# Sheet2.net
KiCad netlist of a schematic drawn in Altium Designer
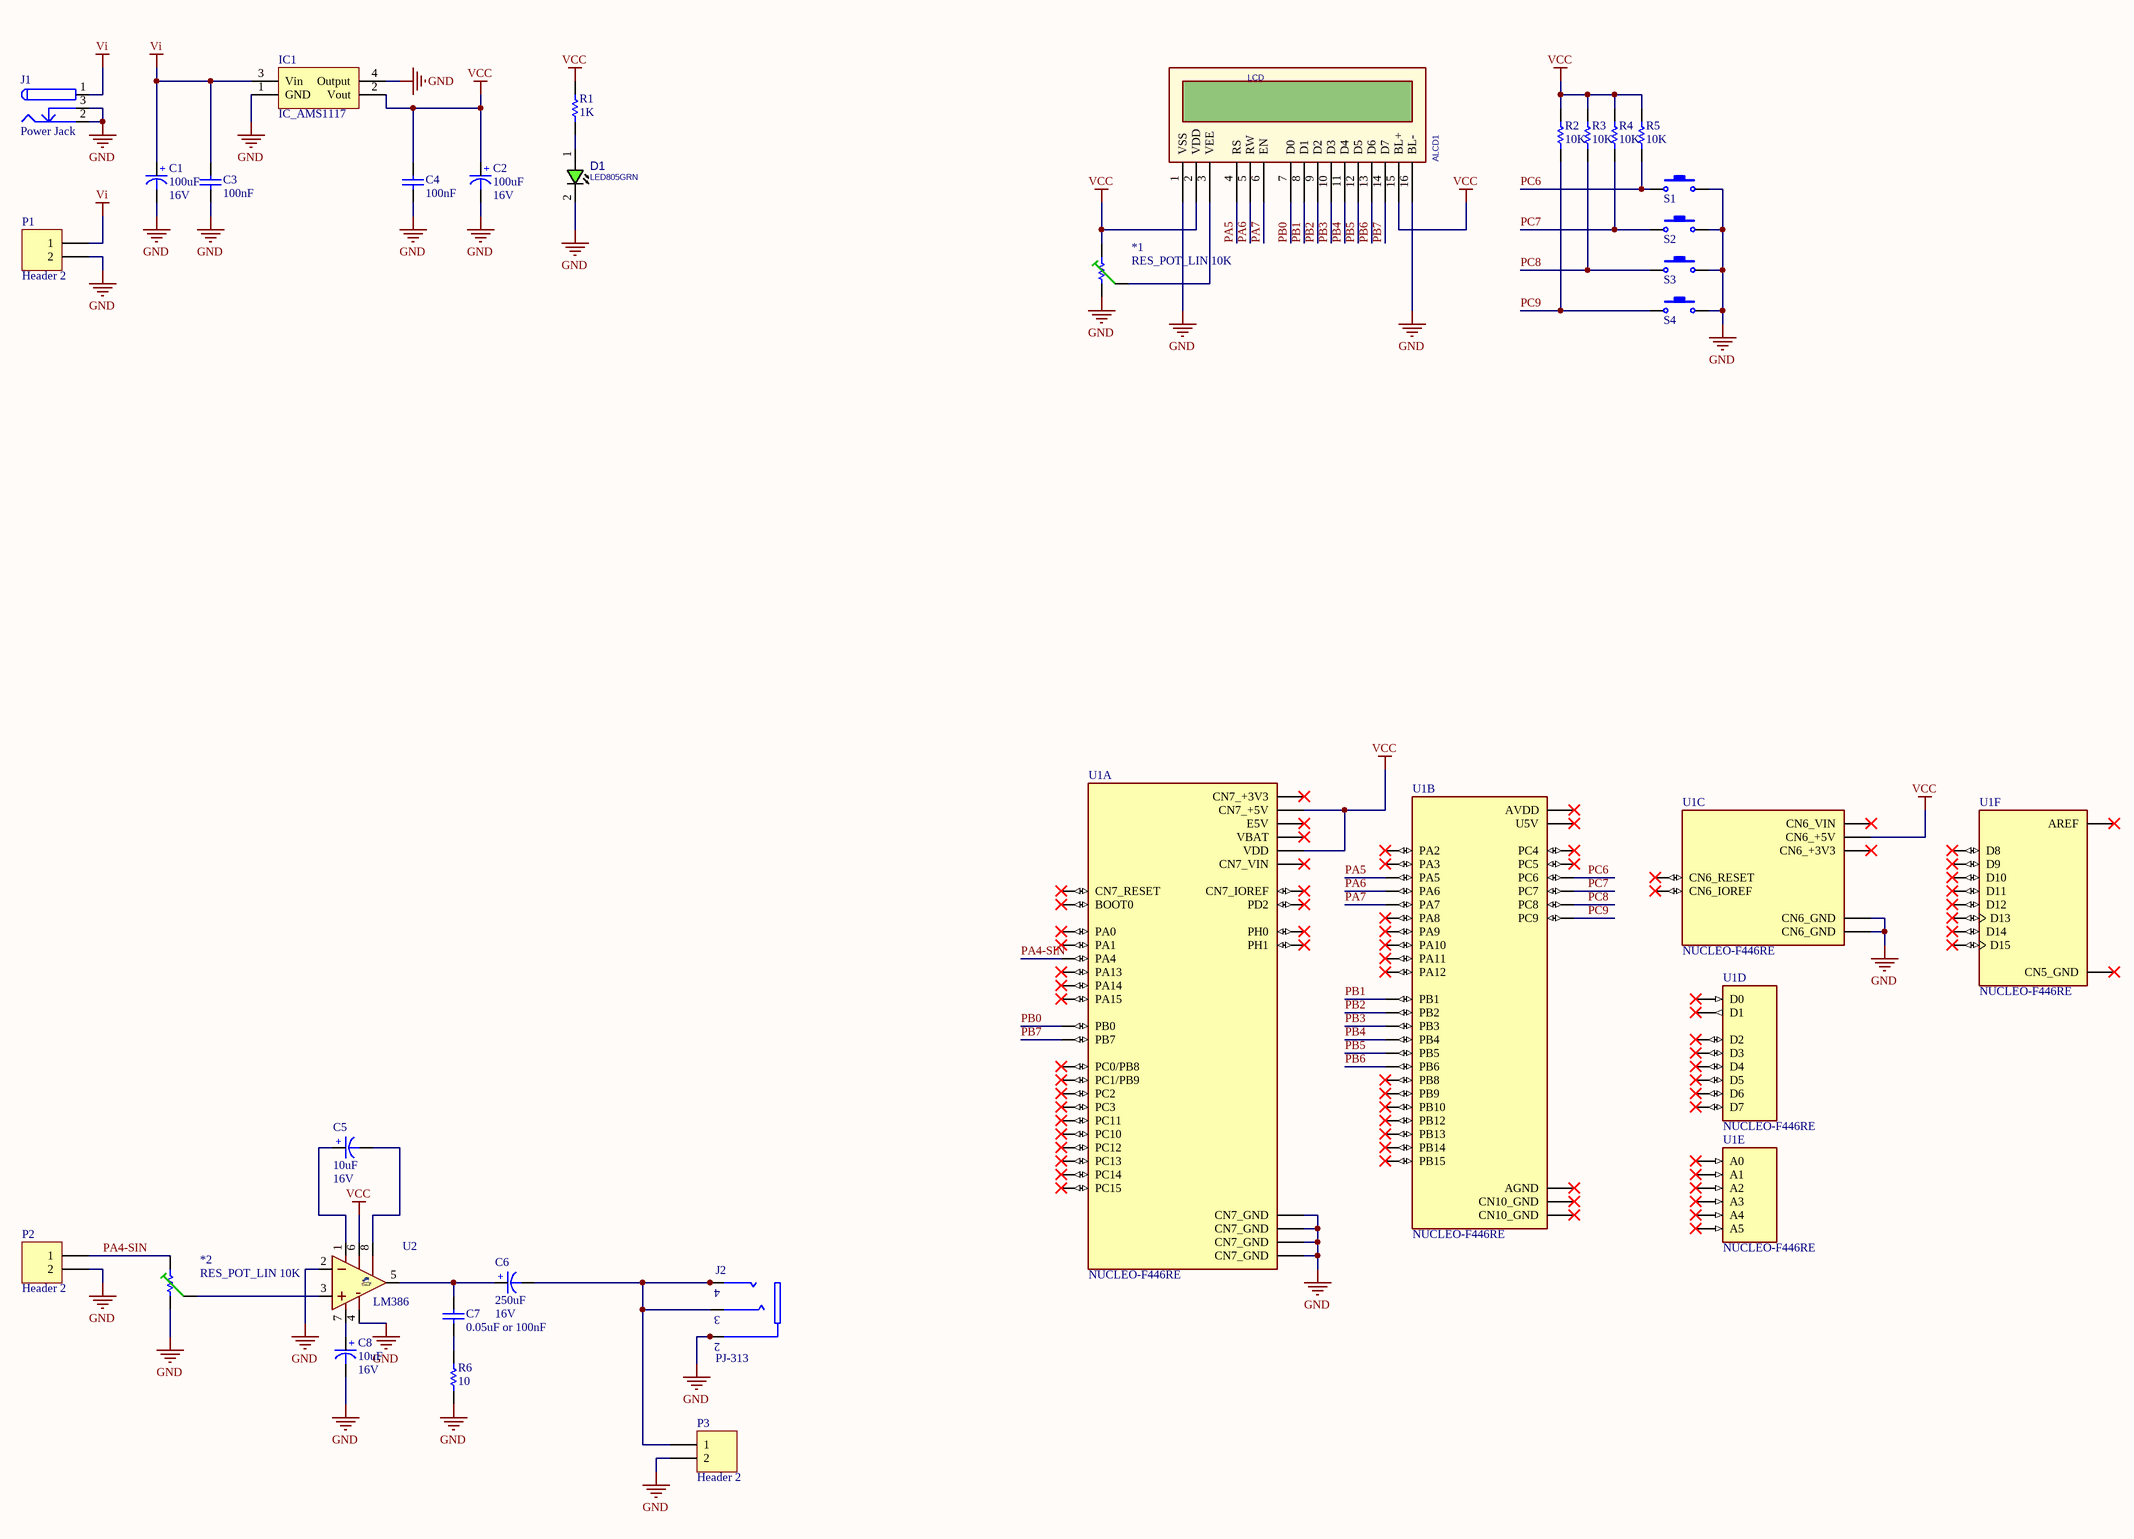
[diagram p0: Sheet2.SchDoc]

(export (version "E")
  (design (tool "Eeschema 10.0.6"))
  (components
    (comp (ref "*1")
      (value "RES_POT_LIN 10K")
      (footprint "3296W")
      (libsource (lib "Passive Components") (part "RES_POT_LIN"))
    )
    (comp (ref "*2")
      (value "RES_POT_LIN 10K")
      (footprint "3296W")
      (libsource (lib "Passive Components") (part "RES_POT_LIN"))
    )
    (comp (ref "ALCD1")
      (value "LCD")
      (footprint "LCD_2X16 GREEN10mm")
      (description "Alphanumic LCD")
      (fields (field (name "DESIGNER") "Abbas Basereh"))
      (libsource (lib "Altium") (part "LCD"))
    )
    (comp (ref "C1")
      (value "100uF")
      (footprint "cap 01")
      (description "Polar Capacitor")
      (fields (field (name "VOLTAGE") "16V") (field (name "DESIGNER") "Saeid Jorablo"))
      (libsource (lib "My_Library") (part "Cap-Polar"))
    )
    (comp (ref "C2")
      (value "100uF")
      (footprint "cap 01")
      (description "Polar Capacitor")
      (fields (field (name "VOLTAGE") "16V") (field (name "DESIGNER") "Saeid Jorablo"))
      (libsource (lib "My_Library") (part "Cap-Polar"))
    )
    (comp (ref "C3")
      (value "100nF")
      (footprint "CAPC3413X12N")
      (description "CAP 0805")
      (fields (field (name "DESIGNER") "Abbas Basereh"))
      (libsource (lib "Altium") (part "CAP SMD 0805"))
    )
    (comp (ref "C4")
      (value "100nF")
      (footprint "CAPC3413X12N")
      (description "CAP 0805")
      (fields (field (name "DESIGNER") "Abbas Basereh"))
      (libsource (lib "Altium") (part "CAP SMD 0805"))
    )
    (comp (ref "C5")
      (value "10uF")
      (footprint "cap 01")
      (description "Polar Capacitor")
      (fields (field (name "VOLTAGE") "16V") (field (name "DESIGNER") "Saeid Jorablo"))
      (libsource (lib "My_Library") (part "Cap-Polar"))
    )
    (comp (ref "C6")
      (value "250uF")
      (footprint "cap 01")
      (description "Polar Capacitor")
      (fields (field (name "VOLTAGE") "16V") (field (name "DESIGNER") "Saeid Jorablo"))
      (libsource (lib "My_Library") (part "Cap-Polar"))
    )
    (comp (ref "C7")
      (value "0.05uF or 100nF")
      (footprint "CAPC3413X12N")
      (description "CAP 0805")
      (fields (field (name "DESIGNER") "Abbas Basereh"))
      (libsource (lib "Altium") (part "CAP SMD 0805"))
    )
    (comp (ref "C8")
      (value "10uF")
      (footprint "cap 01")
      (description "Polar Capacitor")
      (fields (field (name "VOLTAGE") "16V") (field (name "DESIGNER") "Saeid Jorablo"))
      (libsource (lib "My_Library") (part "Cap-Polar"))
    )
    (comp (ref "D1")
      (value "LED805GRN")
      (footprint "LED0805GRN")
      (description "LED, SMD, 0805, GREEN")
      (libsource (lib "led(diode)") (part "LED_SMD_0805_GRN"))
    )
    (comp (ref "IC1")
      (value "IC_AMS1117")
      (footprint "SOT223-4N")
      (description "800mA LOW DROPOUT VOLTAGE REGULATOR")
      (fields
        (field (name "MANUFACTURER") "Advanced Monolithic Systems, Inc.")
        (field (name "DESIGNER") "Eng. Saeid Jorablo")
      )
      (libsource (lib "General 3") (part "IC_AMS1117"))
    )
    (comp (ref "J1")
      (value "Power Jack")
      (footprint "Power Jack")
      (fields (field (name "DESIGNER") "Saeid Jorablo"))
      (libsource (lib "General 2") (part "Power Jack"))
    )
    (comp (ref "J2")
      (value "PJ-313")
      (footprint "PJ-313")
      (description "DC DC Converter Output Input")
      (fields (field (name "MF") "ADC Telecommunications") (field (name "MP") "PJ313"))
      (libsource (lib "PJ-313") (part "PJ-313"))
    )
    (comp (ref "P1")
      (value "Header 2")
      (footprint "HDR1X2")
      (description "Header, 2-Pin")
      (fields (field (name "PUBLISHER") "Altium Limited"))
      (libsource (lib "Altium") (part "Header 2"))
    )
    (comp (ref "P2")
      (value "Header 2")
      (footprint "HDR1X2")
      (description "Header, 2-Pin")
      (fields (field (name "PUBLISHER") "Altium Limited"))
      (libsource (lib "Altium") (part "Header 2"))
    )
    (comp (ref "P3")
      (value "Header 2")
      (footprint "CON_MKDSN1,5/2-5,08")
      (description "Header, 2-Pin")
      (fields (field (name "PUBLISHER") "Altium Limited"))
      (libsource (lib "") (part "Header 2_1"))
    )
    (comp (ref "R1")
      (value "1K")
      (footprint "RESC3413X04N")
      (description "RES 0805")
      (fields (field (name "DESIGNER") "Abbas Basereh"))
      (libsource (lib "General 1") (part "RES 0805 0.125W"))
    )
    (comp (ref "R2")
      (value "10K")
      (footprint "RESC3413X04N")
      (description "RES 0805")
      (fields (field (name "DESIGNER") "Abbas Basereh"))
      (libsource (lib "General 1") (part "RES 0805 0.125W"))
    )
    (comp (ref "R3")
      (value "10K")
      (footprint "RESC3413X04N")
      (description "RES 0805")
      (fields (field (name "DESIGNER") "Abbas Basereh"))
      (libsource (lib "General 1") (part "RES 0805 0.125W"))
    )
    (comp (ref "R4")
      (value "10K")
      (footprint "RESC3413X04N")
      (description "RES 0805")
      (fields (field (name "DESIGNER") "Abbas Basereh"))
      (libsource (lib "General 1") (part "RES 0805 0.125W"))
    )
    (comp (ref "R5")
      (value "10K")
      (footprint "RESC3413X04N")
      (description "RES 0805")
      (fields (field (name "DESIGNER") "Abbas Basereh"))
      (libsource (lib "General 1") (part "RES 0805 0.125W"))
    )
    (comp (ref "R6")
      (value "10")
      (footprint "RESC3413X04N")
      (description "RES 0805")
      (fields (field (name "DESIGNER") "Abbas Basereh"))
      (libsource (lib "General 1") (part "RES 0805 0.125W"))
    )
    (comp (ref "S1")
      (value "Switch PB")
      (footprint "SWPBT_SPST_6X6X10")
      (description "Push Button Switch")
      (libsource (lib "Altium") (part "Switch PB"))
    )
    (comp (ref "S2")
      (value "Switch PB")
      (footprint "SWPBT_SPST_6X6X10")
      (description "Push Button Switch")
      (libsource (lib "Altium") (part "Switch PB"))
    )
    (comp (ref "S3")
      (value "Switch PB")
      (footprint "SWPBT_SPST_6X6X10")
      (description "Push Button Switch")
      (libsource (lib "Altium") (part "Switch PB"))
    )
    (comp (ref "S4")
      (value "Switch PB")
      (footprint "SWPBT_SPST_6X6X10")
      (description "Push Button Switch")
      (libsource (lib "Altium") (part "Switch PB"))
    )
    (comp (ref "U1")
      (value "NUCLEO-F446RE")
      (footprint "MODULE_NUCLEO-F446RE")
      (libsource (lib "NUCLEO-F446RE") (part "NUCLEO-F446RE"))
    )
    (comp (ref "U2")
      (value "LM386")
      (footprint "DIP8")
      (description "AMP, Audio, Low Voltage, Power Amp")
      (fields (field (name "MANF") "Texas Instruments") (field (name "MANF_P#") "LM386N-1"))
      (libsource (lib "amp_audio") (part "LM386_DIP8"))
    )
  )
  (nets
    (net (code "1") (name "/PA4-SIN") (class "Default")
      (node (ref "*2") (pin "1") (pinfunction "CCW_1") (pintype "passive"))
      (node (ref "P2") (pin "1") (pinfunction "1_1") (pintype "passive"))
      (node (ref "U1") (pin "CN7_32") (pinfunction "PA4_CN7_32") (pintype "bidirectional"))
    )
    (net (code "2") (name "/PA5") (class "Default")
      (node (ref "ALCD1") (pin "4") (pinfunction "RS_4") (pintype "passive"))
      (node (ref "U1") (pin "CN10_11") (pinfunction "PA5_CN10_11") (pintype "bidirectional"))
    )
    (net (code "3") (name "/PA6") (class "Default")
      (node (ref "ALCD1") (pin "5") (pinfunction "RW_5") (pintype "passive"))
      (node (ref "U1") (pin "CN10_13") (pinfunction "PA6_CN10_13") (pintype "bidirectional"))
    )
    (net (code "4") (name "/PA7") (class "Default")
      (node (ref "ALCD1") (pin "6") (pinfunction "EN_6") (pintype "passive"))
      (node (ref "U1") (pin "CN10_15") (pinfunction "PA7_CN10_15") (pintype "bidirectional"))
    )
    (net (code "5") (name "/PB0") (class "Default")
      (node (ref "ALCD1") (pin "7") (pinfunction "D0_7") (pintype "passive"))
      (node (ref "U1") (pin "CN7_34") (pinfunction "PB0_CN7_34") (pintype "bidirectional"))
    )
    (net (code "6") (name "/PB1") (class "Default")
      (node (ref "ALCD1") (pin "8") (pinfunction "D1_8") (pintype "passive"))
      (node (ref "U1") (pin "CN10_24") (pinfunction "PB1_CN10_24") (pintype "bidirectional"))
    )
    (net (code "7") (name "/PB2") (class "Default")
      (node (ref "ALCD1") (pin "9") (pinfunction "D2_9") (pintype "passive"))
      (node (ref "U1") (pin "CN10_22") (pinfunction "PB2_CN10_22") (pintype "bidirectional"))
    )
    (net (code "8") (name "/PB3") (class "Default")
      (node (ref "ALCD1") (pin "10") (pinfunction "D3_10") (pintype "passive"))
      (node (ref "U1") (pin "CN10_31") (pinfunction "PB3_CN10_31") (pintype "bidirectional"))
    )
    (net (code "9") (name "/PB4") (class "Default")
      (node (ref "ALCD1") (pin "11") (pinfunction "D4_11") (pintype "passive"))
      (node (ref "U1") (pin "CN10_27") (pinfunction "PB4_CN10_27") (pintype "bidirectional"))
    )
    (net (code "10") (name "/PB5") (class "Default")
      (node (ref "ALCD1") (pin "12") (pinfunction "D5_12") (pintype "passive"))
      (node (ref "U1") (pin "CN10_29") (pinfunction "PB5_CN10_29") (pintype "bidirectional"))
    )
    (net (code "11") (name "/PB6") (class "Default")
      (node (ref "ALCD1") (pin "13") (pinfunction "D6_13") (pintype "passive"))
      (node (ref "U1") (pin "CN10_17") (pinfunction "PB6_CN10_17") (pintype "bidirectional"))
    )
    (net (code "12") (name "/PB7") (class "Default")
      (node (ref "ALCD1") (pin "14") (pinfunction "D7_14") (pintype "passive"))
      (node (ref "U1") (pin "CN7_21") (pinfunction "PB7_CN7_21") (pintype "bidirectional"))
    )
    (net (code "13") (name "/PC6") (class "Default")
      (node (ref "R5") (pin "1") (pinfunction "1_1") (pintype "passive"))
      (node (ref "S1") (pin "1") (pinfunction "1_1") (pintype "passive"))
      (node (ref "U1") (pin "CN10_4") (pinfunction "PC6_CN10_4") (pintype "bidirectional"))
    )
    (net (code "14") (name "/PC7") (class "Default")
      (node (ref "R4") (pin "1") (pinfunction "1_1") (pintype "passive"))
      (node (ref "S2") (pin "1") (pinfunction "1_1") (pintype "passive"))
      (node (ref "U1") (pin "CN10_19") (pinfunction "PC7_CN10_19") (pintype "bidirectional"))
    )
    (net (code "15") (name "/PC8") (class "Default")
      (node (ref "R3") (pin "1") (pinfunction "1_1") (pintype "passive"))
      (node (ref "S3") (pin "1") (pinfunction "1_1") (pintype "passive"))
      (node (ref "U1") (pin "CN10_2") (pinfunction "PC8_CN10_2") (pintype "bidirectional"))
    )
    (net (code "16") (name "/PC9") (class "Default")
      (node (ref "R2") (pin "1") (pinfunction "1_1") (pintype "passive"))
      (node (ref "S4") (pin "1") (pinfunction "1_1") (pintype "passive"))
      (node (ref "U1") (pin "CN10_1") (pinfunction "PC9_CN10_1") (pintype "bidirectional"))
    )
    (net (code "17") (name "GND") (class "Default")
      (node (ref "*1") (pin "3") (pinfunction "CW_3") (pintype "passive"))
      (node (ref "*2") (pin "3") (pinfunction "CW_3") (pintype "passive"))
      (node (ref "ALCD1") (pin "1") (pinfunction "VSS_1") (pintype "passive"))
      (node (ref "ALCD1") (pin "16") (pinfunction "BL-_16") (pintype "passive"))
      (node (ref "C1") (pin "2") (pinfunction "-_2") (pintype "passive"))
      (node (ref "C2") (pin "2") (pinfunction "-_2") (pintype "passive"))
      (node (ref "C3") (pin "1") (pinfunction "1_1") (pintype "passive"))
      (node (ref "C4") (pin "1") (pinfunction "1_1") (pintype "passive"))
      (node (ref "C8") (pin "2") (pinfunction "-_2") (pintype "passive"))
      (node (ref "D1") (pin "2") (pinfunction "CATHODE_2") (pintype "passive"))
      (node (ref "IC1") (pin "1") (pinfunction "GND_1") (pintype "passive"))
      (node (ref "IC1") (pin "4") (pinfunction "Output_4") (pintype "passive"))
      (node (ref "J1") (pin "2") (pinfunction "2_2") (pintype "power_in"))
      (node (ref "J1") (pin "3") (pinfunction "3_3") (pintype "power_in"))
      (node (ref "J2") (pin "2_1") (pinfunction "2_2_1") (pintype "passive"))
      (node (ref "J2") (pin "2_2") (pinfunction "2_2_2") (pintype "passive"))
      (node (ref "P1") (pin "2") (pinfunction "2_2") (pintype "passive"))
      (node (ref "P2") (pin "2") (pinfunction "2_2") (pintype "passive"))
      (node (ref "P3") (pin "2") (pinfunction "2_2") (pintype "passive"))
      (node (ref "R6") (pin "1") (pinfunction "1_1") (pintype "passive"))
      (node (ref "S1") (pin "2") (pinfunction "2_2") (pintype "passive"))
      (node (ref "S2") (pin "2") (pinfunction "2_2") (pintype "passive"))
      (node (ref "S3") (pin "2") (pinfunction "2_2") (pintype "passive"))
      (node (ref "S4") (pin "2") (pinfunction "2_2") (pintype "passive"))
      (node (ref "U1") (pin "CN6_6") (pinfunction "CN6_GND_CN6_6") (pintype "power_in"))
      (node (ref "U1") (pin "CN6_7") (pinfunction "CN6_GND_CN6_7") (pintype "power_in"))
      (node (ref "U1") (pin "CN7_19") (pinfunction "CN7_GND_CN7_19") (pintype "power_in"))
      (node (ref "U1") (pin "CN7_20") (pinfunction "CN7_GND_CN7_20") (pintype "power_in"))
      (node (ref "U1") (pin "CN7_22") (pinfunction "CN7_GND_CN7_22") (pintype "power_in"))
      (node (ref "U1") (pin "CN7_8") (pinfunction "CN7_GND_CN7_8") (pintype "power_in"))
      (node (ref "U2") (pin "2") (pinfunction "IN-_2") (pintype "passive"))
      (node (ref "U2") (pin "4") (pinfunction "GND_4") (pintype "passive"))
    )
    (net (code "18") (name "Net-(*1-WIPER)") (class "Default")
      (node (ref "*1") (pin "2") (pinfunction "WIPER_2") (pintype "passive"))
      (node (ref "ALCD1") (pin "3") (pinfunction "VEE_3") (pintype "passive"))
    )
    (net (code "19") (name "Net-(*2-WIPER)") (class "Default")
      (node (ref "*2") (pin "2") (pinfunction "WIPER_2") (pintype "passive"))
      (node (ref "U2") (pin "3") (pinfunction "IN+_3") (pintype "passive"))
    )
    (net (code "20") (name "Net-(C5-+)") (class "Default")
      (node (ref "C5") (pin "1") (pinfunction "+_1") (pintype "passive"))
      (node (ref "U2") (pin "1") (pinfunction "GAIN_1") (pintype "passive"))
    )
    (net (code "21") (name "Net-(C5--)") (class "Default")
      (node (ref "C5") (pin "2") (pinfunction "-_2") (pintype "passive"))
      (node (ref "U2") (pin "8") (pinfunction "GAIN_8") (pintype "passive"))
    )
    (net (code "22") (name "Net-(C6-+)") (class "Default")
      (node (ref "C6") (pin "1") (pinfunction "+_1") (pintype "passive"))
      (node (ref "C7") (pin "2") (pinfunction "2_2") (pintype "passive"))
      (node (ref "U2") (pin "5") (pinfunction "VOUT_5") (pintype "passive"))
    )
    (net (code "23") (name "Net-(C6--)") (class "Default")
      (node (ref "C6") (pin "2") (pinfunction "-_2") (pintype "passive"))
      (node (ref "J2") (pin "3") (pinfunction "3_3") (pintype "passive"))
      (node (ref "J2") (pin "4_1") (pinfunction "4_4_1") (pintype "passive"))
      (node (ref "J2") (pin "4_2") (pinfunction "4_4_2") (pintype "passive"))
      (node (ref "P3") (pin "1") (pinfunction "1_1") (pintype "passive"))
    )
    (net (code "24") (name "Net-(C7-Pad1)") (class "Default")
      (node (ref "C7") (pin "1") (pinfunction "1_1") (pintype "passive"))
      (node (ref "R6") (pin "2") (pinfunction "2_2") (pintype "passive"))
    )
    (net (code "25") (name "Net-(C8-+)") (class "Default")
      (node (ref "C8") (pin "1") (pinfunction "+_1") (pintype "passive"))
      (node (ref "U2") (pin "7") (pinfunction "BYPASS_7") (pintype "passive"))
    )
    (net (code "26") (name "Net-(D1-ANODE)") (class "Default")
      (node (ref "D1") (pin "1") (pinfunction "ANODE_1") (pintype "passive"))
      (node (ref "R1") (pin "2") (pinfunction "2_2") (pintype "passive"))
    )
    (net (code "27") (name "VCC") (class "Default")
      (node (ref "*1") (pin "1") (pinfunction "CCW_1") (pintype "passive"))
      (node (ref "ALCD1") (pin "15") (pinfunction "BL+_15") (pintype "passive"))
      (node (ref "ALCD1") (pin "2") (pinfunction "VDD_2") (pintype "passive"))
      (node (ref "C2") (pin "1") (pinfunction "+_1") (pintype "passive"))
      (node (ref "C4") (pin "2") (pinfunction "2_2") (pintype "passive"))
      (node (ref "IC1") (pin "2") (pinfunction "Vout_2") (pintype "passive"))
      (node (ref "R1") (pin "1") (pinfunction "1_1") (pintype "passive"))
      (node (ref "R2") (pin "2") (pinfunction "2_2") (pintype "passive"))
      (node (ref "R3") (pin "2") (pinfunction "2_2") (pintype "passive"))
      (node (ref "R4") (pin "2") (pinfunction "2_2") (pintype "passive"))
      (node (ref "R5") (pin "2") (pinfunction "2_2") (pintype "passive"))
      (node (ref "U1") (pin "CN6_5") (pinfunction "CN6_+5V_CN6_5") (pintype "power_in"))
      (node (ref "U1") (pin "CN7_18") (pinfunction "CN7_+5V_CN7_18") (pintype "power_in"))
      (node (ref "U1") (pin "CN7_5") (pinfunction "VDD_CN7_5") (pintype "power_in"))
      (node (ref "U2") (pin "6") (pinfunction "VS_6") (pintype "passive"))
    )
    (net (code "28") (name "Vi") (class "Default")
      (node (ref "C1") (pin "1") (pinfunction "+_1") (pintype "passive"))
      (node (ref "C3") (pin "2") (pinfunction "2_2") (pintype "passive"))
      (node (ref "IC1") (pin "3") (pinfunction "Vin_3") (pintype "passive"))
      (node (ref "J1") (pin "1") (pinfunction "1_1") (pintype "power_in"))
      (node (ref "P1") (pin "1") (pinfunction "1_1") (pintype "passive"))
    )
    (net (code "29") (name "unconnected-(U1A-BOOT0-PadCN7_7)") (class "Default")
      (node (ref "U1") (pin "CN7_7") (pinfunction "BOOT0_CN7_7") (pintype "bidirectional+no_connect"))
    )
    (net (code "30") (name "unconnected-(U1A-CN7_+3V3-PadCN7_16)") (class "Default")
      (node (ref "U1") (pin "CN7_16") (pinfunction "CN7_+3V3_CN7_16") (pintype "power_in+no_connect"))
    )
    (net (code "31") (name "unconnected-(U1A-CN7_IOREF-PadCN7_12)") (class "Default")
      (node (ref "U1") (pin "CN7_12") (pinfunction "CN7_IOREF_CN7_12") (pintype "bidirectional+no_connect"))
    )
    (net (code "32") (name "unconnected-(U1A-CN7_RESET-PadCN7_14)") (class "Default")
      (node (ref "U1") (pin "CN7_14") (pinfunction "CN7_RESET_CN7_14") (pintype "bidirectional+no_connect"))
    )
    (net (code "33") (name "unconnected-(U1A-CN7_VIN-PadCN7_24)") (class "Default")
      (node (ref "U1") (pin "CN7_24") (pinfunction "CN7_VIN_CN7_24") (pintype "power_in+no_connect"))
    )
    (net (code "34") (name "unconnected-(U1A-E5V-PadCN7_6)") (class "Default")
      (node (ref "U1") (pin "CN7_6") (pinfunction "E5V_CN7_6") (pintype "power_in+no_connect"))
    )
    (net (code "35") (name "unconnected-(U1A-PA0-PadCN7_28)") (class "Default")
      (node (ref "U1") (pin "CN7_28") (pinfunction "PA0_CN7_28") (pintype "bidirectional+no_connect"))
    )
    (net (code "36") (name "unconnected-(U1A-PA1-PadCN7_30)") (class "Default")
      (node (ref "U1") (pin "CN7_30") (pinfunction "PA1_CN7_30") (pintype "bidirectional+no_connect"))
    )
    (net (code "37") (name "unconnected-(U1A-PA13-PadCN7_13)") (class "Default")
      (node (ref "U1") (pin "CN7_13") (pinfunction "PA13_CN7_13") (pintype "bidirectional+no_connect"))
    )
    (net (code "38") (name "unconnected-(U1A-PA14-PadCN7_15)") (class "Default")
      (node (ref "U1") (pin "CN7_15") (pinfunction "PA14_CN7_15") (pintype "bidirectional+no_connect"))
    )
    (net (code "39") (name "unconnected-(U1A-PA15-PadCN7_17)") (class "Default")
      (node (ref "U1") (pin "CN7_17") (pinfunction "PA15_CN7_17") (pintype "bidirectional+no_connect"))
    )
    (net (code "40") (name "unconnected-(U1A-PC0{slash}PB8-PadCN7_38)") (class "Default")
      (node (ref "U1") (pin "CN7_38") (pinfunction "PC0/PB8_CN7_38") (pintype "bidirectional+no_connect"))
    )
    (net (code "41") (name "unconnected-(U1A-PC1{slash}PB9-PadCN7_36)") (class "Default")
      (node (ref "U1") (pin "CN7_36") (pinfunction "PC1/PB9_CN7_36") (pintype "bidirectional+no_connect"))
    )
    (net (code "42") (name "unconnected-(U1A-PC2-PadCN7_35)") (class "Default")
      (node (ref "U1") (pin "CN7_35") (pinfunction "PC2_CN7_35") (pintype "bidirectional+no_connect"))
    )
    (net (code "43") (name "unconnected-(U1A-PC3-PadCN7_37)") (class "Default")
      (node (ref "U1") (pin "CN7_37") (pinfunction "PC3_CN7_37") (pintype "bidirectional+no_connect"))
    )
    (net (code "44") (name "unconnected-(U1A-PC10-PadCN7_1)") (class "Default")
      (node (ref "U1") (pin "CN7_1") (pinfunction "PC10_CN7_1") (pintype "bidirectional+no_connect"))
    )
    (net (code "45") (name "unconnected-(U1A-PC11-PadCN7_2)") (class "Default")
      (node (ref "U1") (pin "CN7_2") (pinfunction "PC11_CN7_2") (pintype "bidirectional+no_connect"))
    )
    (net (code "46") (name "unconnected-(U1A-PC12-PadCN7_3)") (class "Default")
      (node (ref "U1") (pin "CN7_3") (pinfunction "PC12_CN7_3") (pintype "bidirectional+no_connect"))
    )
    (net (code "47") (name "unconnected-(U1A-PC13-PadCN7_23)") (class "Default")
      (node (ref "U1") (pin "CN7_23") (pinfunction "PC13_CN7_23") (pintype "bidirectional+no_connect"))
    )
    (net (code "48") (name "unconnected-(U1A-PC14-PadCN7_25)") (class "Default")
      (node (ref "U1") (pin "CN7_25") (pinfunction "PC14_CN7_25") (pintype "bidirectional+no_connect"))
    )
    (net (code "49") (name "unconnected-(U1A-PC15-PadCN7_27)") (class "Default")
      (node (ref "U1") (pin "CN7_27") (pinfunction "PC15_CN7_27") (pintype "bidirectional+no_connect"))
    )
    (net (code "50") (name "unconnected-(U1A-PD2-PadCN7_4)") (class "Default")
      (node (ref "U1") (pin "CN7_4") (pinfunction "PD2_CN7_4") (pintype "bidirectional+no_connect"))
    )
    (net (code "51") (name "unconnected-(U1A-PH0-PadCN7_29)") (class "Default")
      (node (ref "U1") (pin "CN7_29") (pinfunction "PH0_CN7_29") (pintype "bidirectional+no_connect"))
    )
    (net (code "52") (name "unconnected-(U1A-PH1-PadCN7_31)") (class "Default")
      (node (ref "U1") (pin "CN7_31") (pinfunction "PH1_CN7_31") (pintype "bidirectional+no_connect"))
    )
    (net (code "53") (name "unconnected-(U1A-VBAT-PadCN7_33)") (class "Default")
      (node (ref "U1") (pin "CN7_33") (pinfunction "VBAT_CN7_33") (pintype "power_in+no_connect"))
    )
    (net (code "54") (name "unconnected-(U1B-AGND-PadCN10_32)") (class "Default")
      (node (ref "U1") (pin "CN10_32") (pinfunction "AGND_CN10_32") (pintype "power_in+no_connect"))
    )
    (net (code "55") (name "unconnected-(U1B-AVDD-PadCN10_7)") (class "Default")
      (node (ref "U1") (pin "CN10_7") (pinfunction "AVDD_CN10_7") (pintype "power_in+no_connect"))
    )
    (net (code "56") (name "unconnected-(U1B-CN10_GND-PadCN10_9)") (class "Default")
      (node (ref "U1") (pin "CN10_9") (pinfunction "CN10_GND_CN10_9") (pintype "power_in+no_connect"))
    )
    (net (code "57") (name "unconnected-(U1B-CN10_GND-PadCN10_20)") (class "Default")
      (node (ref "U1") (pin "CN10_20") (pinfunction "CN10_GND_CN10_20") (pintype "power_in+no_connect"))
    )
    (net (code "58") (name "unconnected-(U1B-PA2-PadCN10_35)") (class "Default")
      (node (ref "U1") (pin "CN10_35") (pinfunction "PA2_CN10_35") (pintype "bidirectional+no_connect"))
    )
    (net (code "59") (name "unconnected-(U1B-PA3-PadCN10_37)") (class "Default")
      (node (ref "U1") (pin "CN10_37") (pinfunction "PA3_CN10_37") (pintype "bidirectional+no_connect"))
    )
    (net (code "60") (name "unconnected-(U1B-PA8-PadCN10_23)") (class "Default")
      (node (ref "U1") (pin "CN10_23") (pinfunction "PA8_CN10_23") (pintype "bidirectional+no_connect"))
    )
    (net (code "61") (name "unconnected-(U1B-PA9-PadCN10_21)") (class "Default")
      (node (ref "U1") (pin "CN10_21") (pinfunction "PA9_CN10_21") (pintype "bidirectional+no_connect"))
    )
    (net (code "62") (name "unconnected-(U1B-PA10-PadCN10_33)") (class "Default")
      (node (ref "U1") (pin "CN10_33") (pinfunction "PA10_CN10_33") (pintype "bidirectional+no_connect"))
    )
    (net (code "63") (name "unconnected-(U1B-PA11-PadCN10_14)") (class "Default")
      (node (ref "U1") (pin "CN10_14") (pinfunction "PA11_CN10_14") (pintype "bidirectional+no_connect"))
    )
    (net (code "64") (name "unconnected-(U1B-PA12-PadCN10_12)") (class "Default")
      (node (ref "U1") (pin "CN10_12") (pinfunction "PA12_CN10_12") (pintype "bidirectional+no_connect"))
    )
    (net (code "65") (name "unconnected-(U1B-PB8-PadCN10_3)") (class "Default")
      (node (ref "U1") (pin "CN10_3") (pinfunction "PB8_CN10_3") (pintype "bidirectional+no_connect"))
    )
    (net (code "66") (name "unconnected-(U1B-PB9-PadCN10_5)") (class "Default")
      (node (ref "U1") (pin "CN10_5") (pinfunction "PB9_CN10_5") (pintype "bidirectional+no_connect"))
    )
    (net (code "67") (name "unconnected-(U1B-PB10-PadCN10_25)") (class "Default")
      (node (ref "U1") (pin "CN10_25") (pinfunction "PB10_CN10_25") (pintype "bidirectional+no_connect"))
    )
    (net (code "68") (name "unconnected-(U1B-PB12-PadCN10_16)") (class "Default")
      (node (ref "U1") (pin "CN10_16") (pinfunction "PB12_CN10_16") (pintype "bidirectional+no_connect"))
    )
    (net (code "69") (name "unconnected-(U1B-PB13-PadCN10_30)") (class "Default")
      (node (ref "U1") (pin "CN10_30") (pinfunction "PB13_CN10_30") (pintype "bidirectional+no_connect"))
    )
    (net (code "70") (name "unconnected-(U1B-PB14-PadCN10_28)") (class "Default")
      (node (ref "U1") (pin "CN10_28") (pinfunction "PB14_CN10_28") (pintype "bidirectional+no_connect"))
    )
    (net (code "71") (name "unconnected-(U1B-PB15-PadCN10_26)") (class "Default")
      (node (ref "U1") (pin "CN10_26") (pinfunction "PB15_CN10_26") (pintype "bidirectional+no_connect"))
    )
    (net (code "72") (name "unconnected-(U1B-PC4-PadCN10_34)") (class "Default")
      (node (ref "U1") (pin "CN10_34") (pinfunction "PC4_CN10_34") (pintype "bidirectional+no_connect"))
    )
    (net (code "73") (name "unconnected-(U1B-PC5-PadCN10_6)") (class "Default")
      (node (ref "U1") (pin "CN10_6") (pinfunction "PC5_CN10_6") (pintype "bidirectional+no_connect"))
    )
    (net (code "74") (name "unconnected-(U1B-U5V-PadCN10_8)") (class "Default")
      (node (ref "U1") (pin "CN10_8") (pinfunction "U5V_CN10_8") (pintype "power_in+no_connect"))
    )
    (net (code "75") (name "unconnected-(U1C-CN6_+3V3-PadCN6_4)") (class "Default")
      (node (ref "U1") (pin "CN6_4") (pinfunction "CN6_+3V3_CN6_4") (pintype "power_in+no_connect"))
    )
    (net (code "76") (name "unconnected-(U1C-CN6_IOREF-PadCN6_2)") (class "Default")
      (node (ref "U1") (pin "CN6_2") (pinfunction "CN6_IOREF_CN6_2") (pintype "bidirectional+no_connect"))
    )
    (net (code "77") (name "unconnected-(U1C-CN6_RESET-PadCN6_3)") (class "Default")
      (node (ref "U1") (pin "CN6_3") (pinfunction "CN6_RESET_CN6_3") (pintype "bidirectional+no_connect"))
    )
    (net (code "78") (name "unconnected-(U1C-CN6_VIN-PadCN6_8)") (class "Default")
      (node (ref "U1") (pin "CN6_8") (pinfunction "CN6_VIN_CN6_8") (pintype "power_in+no_connect"))
    )
    (net (code "79") (name "unconnected-(U1D-D0-PadCN9_1)") (class "Default")
      (node (ref "U1") (pin "CN9_1") (pinfunction "D0_CN9_1") (pintype "input+no_connect"))
    )
    (net (code "80") (name "unconnected-(U1D-D1-PadCN9_2)") (class "Default")
      (node (ref "U1") (pin "CN9_2") (pinfunction "D1_CN9_2") (pintype "output+no_connect"))
    )
    (net (code "81") (name "unconnected-(U1D-D2-PadCN9_3)") (class "Default")
      (node (ref "U1") (pin "CN9_3") (pinfunction "D2_CN9_3") (pintype "bidirectional+no_connect"))
    )
    (net (code "82") (name "unconnected-(U1D-D3-PadCN9_4)") (class "Default")
      (node (ref "U1") (pin "CN9_4") (pinfunction "D3_CN9_4") (pintype "bidirectional+no_connect"))
    )
    (net (code "83") (name "unconnected-(U1D-D4-PadCN9_5)") (class "Default")
      (node (ref "U1") (pin "CN9_5") (pinfunction "D4_CN9_5") (pintype "bidirectional+no_connect"))
    )
    (net (code "84") (name "unconnected-(U1D-D5-PadCN9_6)") (class "Default")
      (node (ref "U1") (pin "CN9_6") (pinfunction "D5_CN9_6") (pintype "bidirectional+no_connect"))
    )
    (net (code "85") (name "unconnected-(U1D-D6-PadCN9_7)") (class "Default")
      (node (ref "U1") (pin "CN9_7") (pinfunction "D6_CN9_7") (pintype "bidirectional+no_connect"))
    )
    (net (code "86") (name "unconnected-(U1D-D7-PadCN9_8)") (class "Default")
      (node (ref "U1") (pin "CN9_8") (pinfunction "D7_CN9_8") (pintype "bidirectional+no_connect"))
    )
    (net (code "87") (name "unconnected-(U1E-A0-PadCN8_1)") (class "Default")
      (node (ref "U1") (pin "CN8_1") (pinfunction "A0_CN8_1") (pintype "input+no_connect"))
    )
    (net (code "88") (name "unconnected-(U1E-A1-PadCN8_2)") (class "Default")
      (node (ref "U1") (pin "CN8_2") (pinfunction "A1_CN8_2") (pintype "input+no_connect"))
    )
    (net (code "89") (name "unconnected-(U1E-A2-PadCN8_3)") (class "Default")
      (node (ref "U1") (pin "CN8_3") (pinfunction "A2_CN8_3") (pintype "input+no_connect"))
    )
    (net (code "90") (name "unconnected-(U1E-A3-PadCN8_4)") (class "Default")
      (node (ref "U1") (pin "CN8_4") (pinfunction "A3_CN8_4") (pintype "input+no_connect"))
    )
    (net (code "91") (name "unconnected-(U1E-A4-PadCN8_5)") (class "Default")
      (node (ref "U1") (pin "CN8_5") (pinfunction "A4_CN8_5") (pintype "input+no_connect"))
    )
    (net (code "92") (name "unconnected-(U1E-A5-PadCN8_6)") (class "Default")
      (node (ref "U1") (pin "CN8_6") (pinfunction "A5_CN8_6") (pintype "input+no_connect"))
    )
    (net (code "93") (name "unconnected-(U1F-AREF-PadCN5_8)") (class "Default")
      (node (ref "U1") (pin "CN5_8") (pinfunction "AREF_CN5_8") (pintype "power_in+no_connect"))
    )
    (net (code "94") (name "unconnected-(U1F-CN5_GND-PadCN5_7)") (class "Default")
      (node (ref "U1") (pin "CN5_7") (pinfunction "CN5_GND_CN5_7") (pintype "power_in+no_connect"))
    )
    (net (code "95") (name "unconnected-(U1F-D8-PadCN5_1)") (class "Default")
      (node (ref "U1") (pin "CN5_1") (pinfunction "D8_CN5_1") (pintype "bidirectional+no_connect"))
    )
    (net (code "96") (name "unconnected-(U1F-D9-PadCN5_2)") (class "Default")
      (node (ref "U1") (pin "CN5_2") (pinfunction "D9_CN5_2") (pintype "bidirectional+no_connect"))
    )
    (net (code "97") (name "unconnected-(U1F-D10-PadCN5_3)") (class "Default")
      (node (ref "U1") (pin "CN5_3") (pinfunction "D10_CN5_3") (pintype "bidirectional+no_connect"))
    )
    (net (code "98") (name "unconnected-(U1F-D11-PadCN5_4)") (class "Default")
      (node (ref "U1") (pin "CN5_4") (pinfunction "D11_CN5_4") (pintype "bidirectional+no_connect"))
    )
    (net (code "99") (name "unconnected-(U1F-D12-PadCN5_5)") (class "Default")
      (node (ref "U1") (pin "CN5_5") (pinfunction "D12_CN5_5") (pintype "bidirectional+no_connect"))
    )
    (net (code "100") (name "unconnected-(U1F-D13-PadCN5_6)") (class "Default")
      (node (ref "U1") (pin "CN5_6") (pinfunction "D13_CN5_6") (pintype "bidirectional+no_connect"))
    )
    (net (code "101") (name "unconnected-(U1F-D14-PadCN5_9)") (class "Default")
      (node (ref "U1") (pin "CN5_9") (pinfunction "D14_CN5_9") (pintype "bidirectional+no_connect"))
    )
    (net (code "102") (name "unconnected-(U1F-D15-PadCN5_10)") (class "Default")
      (node (ref "U1") (pin "CN5_10") (pinfunction "D15_CN5_10") (pintype "bidirectional+no_connect"))
    )
  )
)
